# energy_monitor.net
KiCad netlist of a schematic drawn in EAGLE
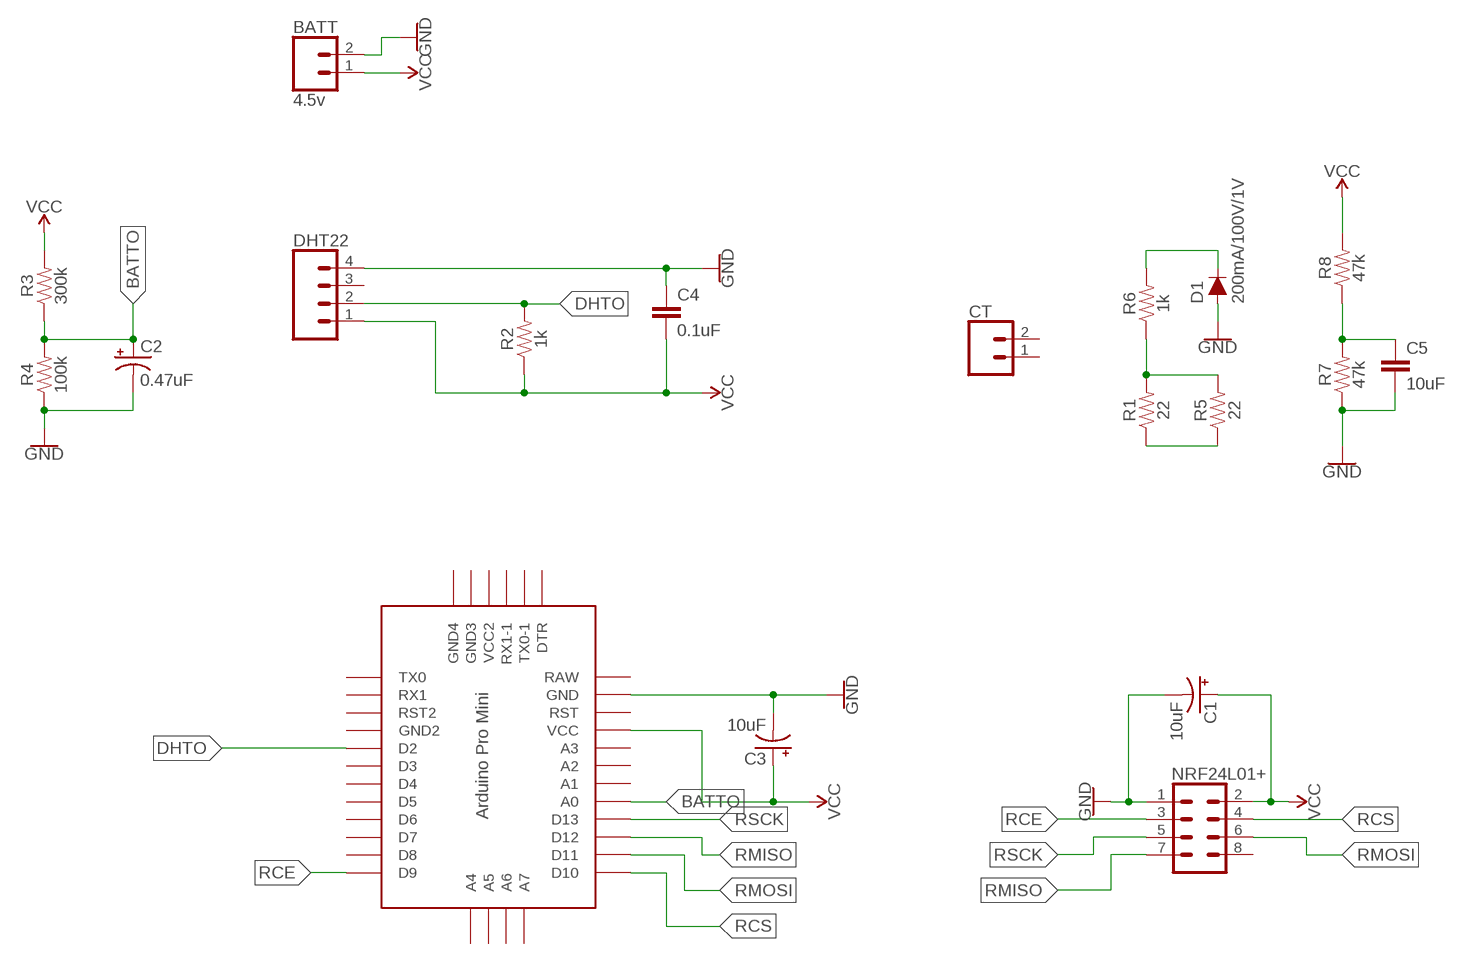
[diagram p0: schematic, sheet 1]

(export (version "E")
  (design (tool "Eeschema 10.0.6"))
  (components
    (comp (ref "BATT")
      (value "4.5v")
      (footprint "eagle-import:1X02")
      (libsource (lib "eagle-import") (part "CONN_02"))
    )
    (comp (ref "C1")
      (value "10uF")
      (footprint "eagle-import:CPOL-RADIAL-2.5MM-5MM")
      (libsource (lib "eagle-import") (part "10UF-POLAR-RADIAL-2.5MM-25V-20%"))
    )
    (comp (ref "C2")
      (value "0.47uF")
      (footprint "eagle-import:CPOL-RADIAL-2.5MM-5MM")
      (libsource (lib "eagle-import") (part "10UF-POLAR-RADIAL-2.5MM-25V-20%"))
    )
    (comp (ref "C3")
      (value "10uF")
      (footprint "eagle-import:CPOL-RADIAL-2.5MM-5MM")
      (libsource (lib "eagle-import") (part "10UF-POLAR-RADIAL-2.5MM-25V-20%"))
    )
    (comp (ref "C4")
      (value "0.1uF")
      (footprint "eagle-import:CAP-PTH-SMALL-KIT")
      (libsource (lib "eagle-import") (part "0.1UF-KIT-EZ-50V-20%"))
    )
    (comp (ref "C5")
      (value "10uF")
      (footprint "eagle-import:0603")
      (libsource (lib "eagle-import") (part "10UF-0603-6.3V-20%"))
    )
    (comp (ref "CT")
      (value "CONN_02")
      (footprint "eagle-import:1X02")
      (libsource (lib "eagle-import") (part "CONN_02"))
    )
    (comp (ref "D1")
      (value "200mA/100V/1V")
      (footprint "eagle-import:DIODE-1N4148")
      (libsource (lib "eagle-import") (part "DIODE-1N4148"))
    )
    (comp (ref "DHT22")
      (value "CONN_04")
      (footprint "eagle-import:1X04")
      (libsource (lib "eagle-import") (part "CONN_04"))
    )
    (comp (ref "IC1")
      (value "PRO-MINI")
      (footprint "eagle-import:PRO-MINI")
      (libsource (lib "eagle-import") (part "PRO-MINI"))
    )
    (comp (ref "NRF24L01+")
      (value "CONN_04X2")
      (footprint "eagle-import:2X4")
      (libsource (lib "eagle-import") (part "CONN_04X2"))
    )
    (comp (ref "R1")
      (value "22")
      (footprint "eagle-import:0603")
      (libsource (lib "eagle-import") (part "22OHM-0603-1/10W-1%"))
    )
    (comp (ref "R2")
      (value "1k")
      (footprint "eagle-import:AXIAL-0.3")
      (libsource (lib "eagle-import") (part "1KOHM-HORIZ-1/4W-5%"))
    )
    (comp (ref "R3")
      (value "300k")
      (footprint "eagle-import:0603")
      (libsource (lib "eagle-import") (part "300KOHM-0603-1/10W-1%"))
    )
    (comp (ref "R4")
      (value "100k")
      (footprint "eagle-import:AXIAL-0.3")
      (libsource (lib "eagle-import") (part "100KOHM-HORIZ-1/4W-1%"))
    )
    (comp (ref "R5")
      (value "22")
      (footprint "eagle-import:0603")
      (libsource (lib "eagle-import") (part "22OHM-0603-1/10W-1%"))
    )
    (comp (ref "R6")
      (value "1k")
      (footprint "eagle-import:0603")
      (libsource (lib "eagle-import") (part "1KOHM-0603-1/10W-1%"))
    )
    (comp (ref "R7")
      (value "47k")
      (footprint "eagle-import:0603")
      (libsource (lib "eagle-import") (part "47KOHM-0603-1/10W-1%"))
    )
    (comp (ref "R8")
      (value "47k")
      (footprint "eagle-import:0603")
      (libsource (lib "eagle-import") (part "47KOHM-0603-1/10W-1%"))
    )
  )
  (nets
    (net (code "1") (name "/RAW") (class "Default")
      (node (ref "IC1") (pin "RAW") (pinfunction "RAW_RAW") (pintype "power_in"))
    )
    (net (code "2") (name "BATTO") (class "Default")
      (node (ref "C2") (pin "1") (pinfunction "+_1") (pintype "passive"))
      (node (ref "IC1") (pin "A0") (pinfunction "A0_A0") (pintype "bidirectional"))
      (node (ref "R3") (pin "1") (pinfunction "1_1") (pintype "passive"))
      (node (ref "R4") (pin "P$2") (pinfunction "2_P$2") (pintype "passive"))
    )
    (net (code "3") (name "DHTO") (class "Default")
      (node (ref "DHT22") (pin "2") (pinfunction "2_2") (pintype "passive"))
      (node (ref "IC1") (pin "D2") (pinfunction "D2_D2") (pintype "bidirectional"))
      (node (ref "R2") (pin "P$2") (pinfunction "2_P$2") (pintype "passive"))
    )
    (net (code "4") (name "GND") (class "Default")
      (node (ref "BATT") (pin "2") (pinfunction "2_2") (pintype "passive"))
      (node (ref "C1") (pin "2") (pinfunction "-_2") (pintype "passive"))
      (node (ref "C2") (pin "2") (pinfunction "-_2") (pintype "passive"))
      (node (ref "C3") (pin "2") (pinfunction "-_2") (pintype "passive"))
      (node (ref "C4") (pin "1") (pinfunction "1_1") (pintype "passive"))
      (node (ref "C5") (pin "2") (pinfunction "2_2") (pintype "passive"))
      (node (ref "D1") (pin "A") (pinfunction "A_A") (pintype "passive"))
      (node (ref "DHT22") (pin "4") (pinfunction "4_4") (pintype "passive"))
      (node (ref "IC1") (pin "GND") (pinfunction "GND_GND") (pintype "input"))
      (node (ref "NRF24L01+") (pin "1") (pinfunction "1_1") (pintype "passive"))
      (node (ref "R4") (pin "P$1") (pinfunction "1_P$1") (pintype "passive"))
      (node (ref "R7") (pin "1") (pinfunction "1_1") (pintype "passive"))
    )
    (net (code "5") (name "Net-(C5-Pad1)") (class "Default")
      (node (ref "C5") (pin "1") (pinfunction "1_1") (pintype "passive"))
      (node (ref "R7") (pin "2") (pinfunction "2_2") (pintype "passive"))
      (node (ref "R8") (pin "1") (pinfunction "1_1") (pintype "passive"))
    )
    (net (code "6") (name "Net-(D1-PadC)") (class "Default")
      (node (ref "D1") (pin "C") (pinfunction "C_C") (pintype "passive"))
      (node (ref "R6") (pin "2") (pinfunction "2_2") (pintype "passive"))
    )
    (net (code "7") (name "Net-(R1-Pad1)") (class "Default")
      (node (ref "R1") (pin "1") (pinfunction "1_1") (pintype "passive"))
      (node (ref "R5") (pin "1") (pinfunction "1_1") (pintype "passive"))
    )
    (net (code "8") (name "Net-(R1-Pad2)") (class "Default")
      (node (ref "R1") (pin "2") (pinfunction "2_2") (pintype "passive"))
      (node (ref "R5") (pin "2") (pinfunction "2_2") (pintype "passive"))
      (node (ref "R6") (pin "1") (pinfunction "1_1") (pintype "passive"))
    )
    (net (code "9") (name "RCE") (class "Default")
      (node (ref "IC1") (pin "D9") (pinfunction "D9_D9") (pintype "bidirectional"))
      (node (ref "NRF24L01+") (pin "3") (pinfunction "3_3") (pintype "passive"))
    )
    (net (code "10") (name "RCS") (class "Default")
      (node (ref "IC1") (pin "D10") (pinfunction "D10_D10") (pintype "bidirectional"))
      (node (ref "NRF24L01+") (pin "4") (pinfunction "4_4") (pintype "passive"))
    )
    (net (code "11") (name "RMISO") (class "Default")
      (node (ref "IC1") (pin "D12") (pinfunction "D12_D12") (pintype "bidirectional"))
      (node (ref "NRF24L01+") (pin "7") (pinfunction "7_7") (pintype "passive"))
    )
    (net (code "12") (name "RMOSI") (class "Default")
      (node (ref "IC1") (pin "D11") (pinfunction "D11_D11") (pintype "bidirectional"))
      (node (ref "NRF24L01+") (pin "6") (pinfunction "6_6") (pintype "passive"))
    )
    (net (code "13") (name "RSCK") (class "Default")
      (node (ref "IC1") (pin "D13") (pinfunction "D13_D13") (pintype "bidirectional"))
      (node (ref "NRF24L01+") (pin "5") (pinfunction "5_5") (pintype "passive"))
    )
    (net (code "14") (name "VCC") (class "Default")
      (node (ref "BATT") (pin "1") (pinfunction "1_1") (pintype "passive"))
      (node (ref "C1") (pin "1") (pinfunction "+_1") (pintype "passive"))
      (node (ref "C3") (pin "1") (pinfunction "+_1") (pintype "passive"))
      (node (ref "C4") (pin "2") (pinfunction "2_2") (pintype "passive"))
      (node (ref "DHT22") (pin "1") (pinfunction "1_1") (pintype "passive"))
      (node (ref "IC1") (pin "VCC") (pinfunction "VCC_VCC") (pintype "bidirectional"))
      (node (ref "NRF24L01+") (pin "2") (pinfunction "2_2") (pintype "passive"))
      (node (ref "R2") (pin "P$1") (pinfunction "1_P$1") (pintype "passive"))
      (node (ref "R3") (pin "2") (pinfunction "2_2") (pintype "passive"))
      (node (ref "R8") (pin "2") (pinfunction "2_2") (pintype "passive"))
    )
    (net (code "15") (name "unconnected-(CT-Pad1)") (class "Default")
      (node (ref "CT") (pin "1") (pinfunction "1_1") (pintype "passive"))
    )
    (net (code "16") (name "unconnected-(CT-Pad2)") (class "Default")
      (node (ref "CT") (pin "2") (pinfunction "2_2") (pintype "passive"))
    )
    (net (code "17") (name "unconnected-(DHT22-Pad3)") (class "Default")
      (node (ref "DHT22") (pin "3") (pinfunction "3_3") (pintype "passive"))
    )
    (net (code "18") (name "unconnected-(IC1-GND2-PadGND1)") (class "Default")
      (node (ref "IC1") (pin "GND1") (pinfunction "GND2_GND1") (pintype "bidirectional"))
    )
    (net (code "19") (name "unconnected-(IC1-GND4-PadGND2)") (class "Default")
      (node (ref "IC1") (pin "GND2") (pinfunction "GND4_GND2") (pintype "bidirectional"))
    )
    (net (code "20") (name "unconnected-(IC1-PadA1)") (class "Default")
      (node (ref "IC1") (pin "A1") (pinfunction "A1_A1") (pintype "bidirectional"))
    )
    (net (code "21") (name "unconnected-(IC1-PadA2)") (class "Default")
      (node (ref "IC1") (pin "A2") (pinfunction "A2_A2") (pintype "bidirectional"))
    )
    (net (code "22") (name "unconnected-(IC1-PadA3)") (class "Default")
      (node (ref "IC1") (pin "A3") (pinfunction "A3_A3") (pintype "bidirectional"))
    )
    (net (code "23") (name "unconnected-(IC1-PadA4)") (class "Default")
      (node (ref "IC1") (pin "A4") (pinfunction "A4_A4") (pintype "bidirectional"))
    )
    (net (code "24") (name "unconnected-(IC1-PadA5)") (class "Default")
      (node (ref "IC1") (pin "A5") (pinfunction "A5_A5") (pintype "bidirectional"))
    )
    (net (code "25") (name "unconnected-(IC1-PadA6)") (class "Default")
      (node (ref "IC1") (pin "A6") (pinfunction "A6_A6") (pintype "bidirectional"))
    )
    (net (code "26") (name "unconnected-(IC1-PadA7)") (class "Default")
      (node (ref "IC1") (pin "A7") (pinfunction "A7_A7") (pintype "bidirectional"))
    )
    (net (code "27") (name "unconnected-(IC1-PadD3)") (class "Default")
      (node (ref "IC1") (pin "D3") (pinfunction "D3_D3") (pintype "bidirectional"))
    )
    (net (code "28") (name "unconnected-(IC1-PadD4)") (class "Default")
      (node (ref "IC1") (pin "D4") (pinfunction "D4_D4") (pintype "bidirectional"))
    )
    (net (code "29") (name "unconnected-(IC1-PadD5)") (class "Default")
      (node (ref "IC1") (pin "D5") (pinfunction "D5_D5") (pintype "bidirectional"))
    )
    (net (code "30") (name "unconnected-(IC1-PadD6)") (class "Default")
      (node (ref "IC1") (pin "D6") (pinfunction "D6_D6") (pintype "bidirectional"))
    )
    (net (code "31") (name "unconnected-(IC1-PadD7)") (class "Default")
      (node (ref "IC1") (pin "D7") (pinfunction "D7_D7") (pintype "bidirectional"))
    )
    (net (code "32") (name "unconnected-(IC1-PadD8)") (class "Default")
      (node (ref "IC1") (pin "D8") (pinfunction "D8_D8") (pintype "bidirectional"))
    )
    (net (code "33") (name "unconnected-(IC1-PadDTR)") (class "Default")
      (node (ref "IC1") (pin "DTR") (pinfunction "DTR_DTR") (pintype "bidirectional"))
    )
    (net (code "34") (name "unconnected-(IC1-PadGND3)") (class "Default")
      (node (ref "IC1") (pin "GND3") (pinfunction "GND3_GND3") (pintype "bidirectional"))
    )
    (net (code "35") (name "unconnected-(IC1-PadRST)") (class "Default")
      (node (ref "IC1") (pin "RST") (pinfunction "RST_RST") (pintype "bidirectional"))
    )
    (net (code "36") (name "unconnected-(IC1-PadRX1)") (class "Default")
      (node (ref "IC1") (pin "RX1") (pinfunction "RX1_RX1") (pintype "bidirectional"))
    )
    (net (code "37") (name "unconnected-(IC1-PadRX1-1)") (class "Default")
      (node (ref "IC1") (pin "RX1-1") (pinfunction "RX1-1_RX1-1") (pintype "bidirectional"))
    )
    (net (code "38") (name "unconnected-(IC1-PadTX0)") (class "Default")
      (node (ref "IC1") (pin "TX0") (pinfunction "TX0_TX0") (pintype "bidirectional"))
    )
    (net (code "39") (name "unconnected-(IC1-PadTX0-1)") (class "Default")
      (node (ref "IC1") (pin "TX0-1") (pinfunction "TX0-1_TX0-1") (pintype "bidirectional"))
    )
    (net (code "40") (name "unconnected-(IC1-RST2-PadRST1)") (class "Default")
      (node (ref "IC1") (pin "RST1") (pinfunction "RST2_RST1") (pintype "bidirectional"))
    )
    (net (code "41") (name "unconnected-(IC1-VCC2-PadVCC1)") (class "Default")
      (node (ref "IC1") (pin "VCC1") (pinfunction "VCC2_VCC1") (pintype "bidirectional"))
    )
    (net (code "42") (name "unconnected-(NRF24L01+-Pad8)") (class "Default")
      (node (ref "NRF24L01+") (pin "8") (pinfunction "8_8") (pintype "passive"))
    )
  )
)
